# Lixieuhr-Segment.net
KiCad netlist of a schematic drawn in EAGLE
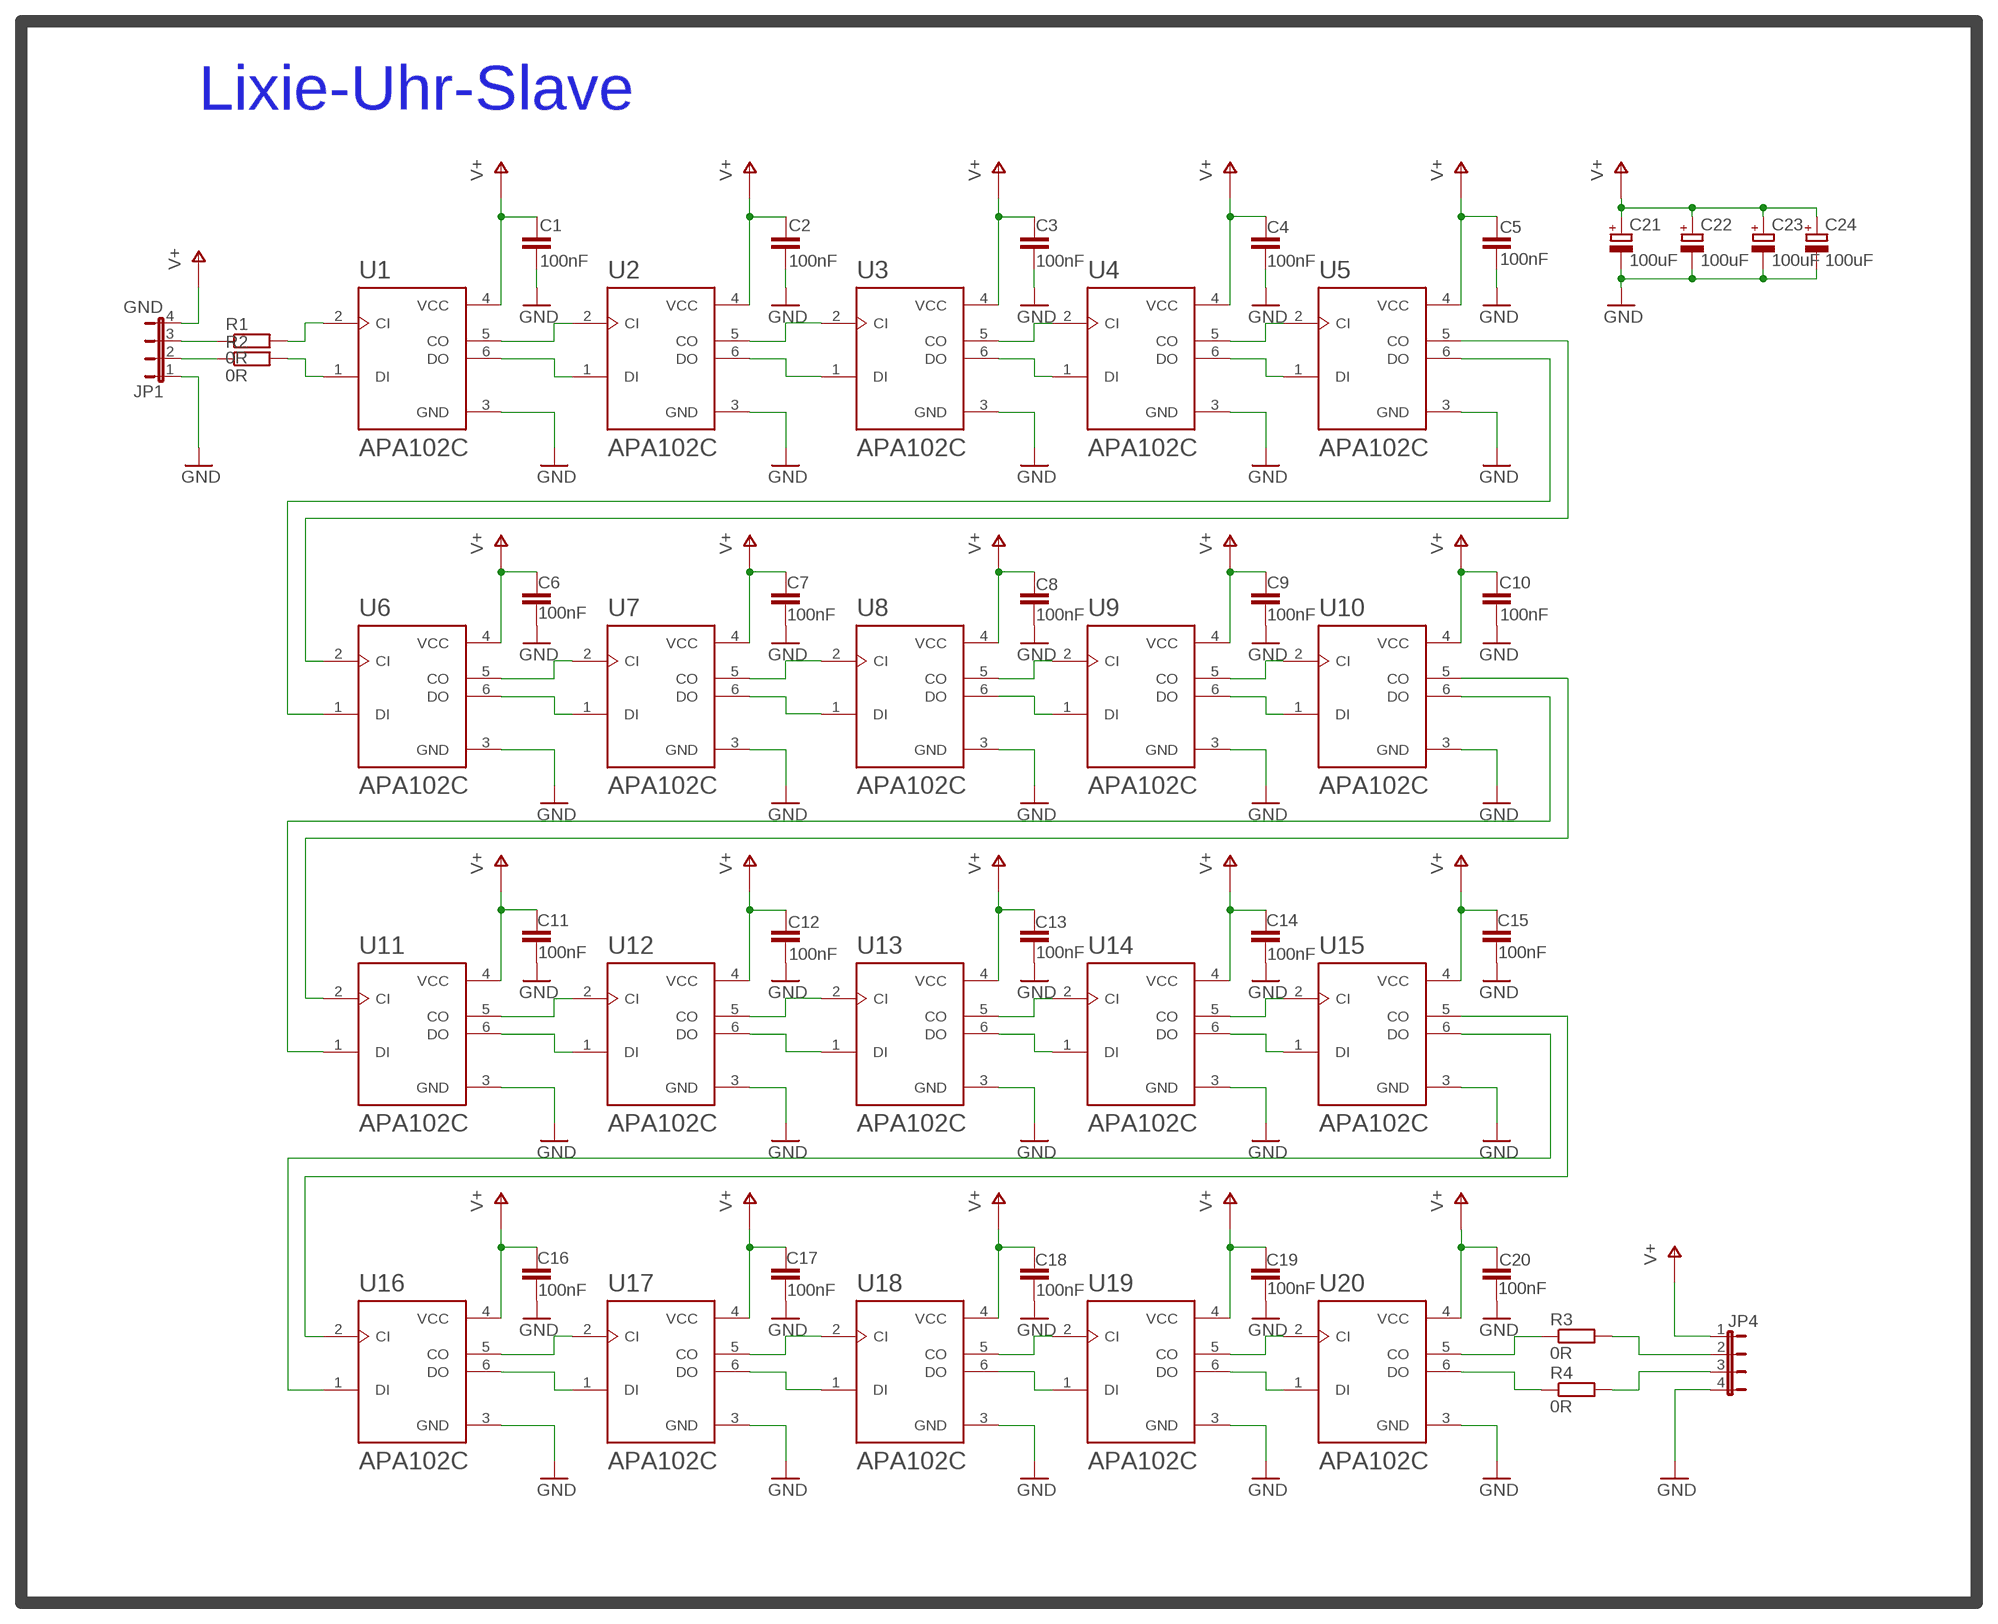
[diagram p0: schematic, sheet 1]

(export (version "E")
  (design (tool "Eeschema 10.0.6"))
  (components
    (comp (ref "C1")
      (value "100nF")
      (footprint "eagle-import:C0805")
      (libsource (lib "eagle-import") (part "C-0805"))
    )
    (comp (ref "C2")
      (value "100nF")
      (footprint "eagle-import:C0805")
      (libsource (lib "eagle-import") (part "C-0805"))
    )
    (comp (ref "C3")
      (value "100nF")
      (footprint "eagle-import:C0805")
      (libsource (lib "eagle-import") (part "C-0805"))
    )
    (comp (ref "C4")
      (value "100nF")
      (footprint "eagle-import:C0805")
      (libsource (lib "eagle-import") (part "C-0805"))
    )
    (comp (ref "C5")
      (value "100nF")
      (footprint "eagle-import:C0805")
      (libsource (lib "eagle-import") (part "C-0805"))
    )
    (comp (ref "C6")
      (value "100nF")
      (footprint "eagle-import:C0805")
      (libsource (lib "eagle-import") (part "C-0805"))
    )
    (comp (ref "C7")
      (value "100nF")
      (footprint "eagle-import:C0805")
      (libsource (lib "eagle-import") (part "C-0805"))
    )
    (comp (ref "C8")
      (value "100nF")
      (footprint "eagle-import:C0805")
      (libsource (lib "eagle-import") (part "C-0805"))
    )
    (comp (ref "C9")
      (value "100nF")
      (footprint "eagle-import:C0805")
      (libsource (lib "eagle-import") (part "C-0805"))
    )
    (comp (ref "C10")
      (value "100nF")
      (footprint "eagle-import:C0805")
      (libsource (lib "eagle-import") (part "C-0805"))
    )
    (comp (ref "C11")
      (value "100nF")
      (footprint "eagle-import:C0805")
      (libsource (lib "eagle-import") (part "C-0805"))
    )
    (comp (ref "C12")
      (value "100nF")
      (footprint "eagle-import:C0805")
      (libsource (lib "eagle-import") (part "C-0805"))
    )
    (comp (ref "C13")
      (value "100nF")
      (footprint "eagle-import:C0805")
      (libsource (lib "eagle-import") (part "C-0805"))
    )
    (comp (ref "C14")
      (value "100nF")
      (footprint "eagle-import:C0805")
      (libsource (lib "eagle-import") (part "C-0805"))
    )
    (comp (ref "C15")
      (value "100nF")
      (footprint "eagle-import:C0805")
      (libsource (lib "eagle-import") (part "C-0805"))
    )
    (comp (ref "C16")
      (value "100nF")
      (footprint "eagle-import:C0805")
      (libsource (lib "eagle-import") (part "C-0805"))
    )
    (comp (ref "C17")
      (value "100nF")
      (footprint "eagle-import:C0805")
      (libsource (lib "eagle-import") (part "C-0805"))
    )
    (comp (ref "C18")
      (value "100nF")
      (footprint "eagle-import:C0805")
      (libsource (lib "eagle-import") (part "C-0805"))
    )
    (comp (ref "C19")
      (value "100nF")
      (footprint "eagle-import:C0805")
      (libsource (lib "eagle-import") (part "C-0805"))
    )
    (comp (ref "C20")
      (value "100nF")
      (footprint "eagle-import:C0805")
      (libsource (lib "eagle-import") (part "C-0805"))
    )
    (comp (ref "C21")
      (value "100uF")
      (footprint "eagle-import:153CLV-0405")
      (libsource (lib "eagle-import") (part "CPOL-EU153CLV-0405"))
    )
    (comp (ref "C22")
      (value "100uF")
      (footprint "eagle-import:153CLV-0405")
      (libsource (lib "eagle-import") (part "CPOL-EU153CLV-0405"))
    )
    (comp (ref "C23")
      (value "100uF")
      (footprint "eagle-import:153CLV-0405")
      (libsource (lib "eagle-import") (part "CPOL-EU153CLV-0405"))
    )
    (comp (ref "C24")
      (value "100uF")
      (footprint "eagle-import:153CLV-0405")
      (libsource (lib "eagle-import") (part "CPOL-EU153CLV-0405"))
    )
    (comp (ref "JP1")
      (value "GND")
      (footprint "eagle-import:JP4")
      (libsource (lib "eagle-import") (part "JP4E"))
    )
    (comp (ref "JP4")
      (value "JP4E")
      (footprint "eagle-import:JP4")
      (libsource (lib "eagle-import") (part "JP4E"))
    )
    (comp (ref "R1")
      (value "0R")
      (footprint "eagle-import:R1206")
      (libsource (lib "eagle-import") (part "R-R1206"))
    )
    (comp (ref "R2")
      (value "0R")
      (footprint "eagle-import:R1206")
      (libsource (lib "eagle-import") (part "R-R1206"))
    )
    (comp (ref "R3")
      (value "0R")
      (footprint "eagle-import:R1206")
      (libsource (lib "eagle-import") (part "R-R1206"))
    )
    (comp (ref "R4")
      (value "0R")
      (footprint "eagle-import:R1206")
      (libsource (lib "eagle-import") (part "R-R1206"))
    )
    (comp (ref "U1")
      (value "APA102C")
      (footprint "eagle-import:SON160P500X500X140-6N")
      (fields (field (name "MF") "Shiji Lighting"))
      (libsource (lib "eagle-import") (part "APA102C"))
    )
    (comp (ref "U2")
      (value "APA102C")
      (footprint "eagle-import:SON160P500X500X140-6N")
      (fields (field (name "MF") "Shiji Lighting"))
      (libsource (lib "eagle-import") (part "APA102C"))
    )
    (comp (ref "U3")
      (value "APA102C")
      (footprint "eagle-import:SON160P500X500X140-6N")
      (fields (field (name "MF") "Shiji Lighting"))
      (libsource (lib "eagle-import") (part "APA102C"))
    )
    (comp (ref "U4")
      (value "APA102C")
      (footprint "eagle-import:SON160P500X500X140-6N")
      (fields (field (name "MF") "Shiji Lighting"))
      (libsource (lib "eagle-import") (part "APA102C"))
    )
    (comp (ref "U5")
      (value "APA102C")
      (footprint "eagle-import:SON160P500X500X140-6N")
      (fields (field (name "MF") "Shiji Lighting"))
      (libsource (lib "eagle-import") (part "APA102C"))
    )
    (comp (ref "U6")
      (value "APA102C")
      (footprint "eagle-import:SON160P500X500X140-6N")
      (fields (field (name "MF") "Shiji Lighting"))
      (libsource (lib "eagle-import") (part "APA102C"))
    )
    (comp (ref "U7")
      (value "APA102C")
      (footprint "eagle-import:SON160P500X500X140-6N")
      (fields (field (name "MF") "Shiji Lighting"))
      (libsource (lib "eagle-import") (part "APA102C"))
    )
    (comp (ref "U8")
      (value "APA102C")
      (footprint "eagle-import:SON160P500X500X140-6N")
      (fields (field (name "MF") "Shiji Lighting"))
      (libsource (lib "eagle-import") (part "APA102C"))
    )
    (comp (ref "U9")
      (value "APA102C")
      (footprint "eagle-import:SON160P500X500X140-6N")
      (fields (field (name "MF") "Shiji Lighting"))
      (libsource (lib "eagle-import") (part "APA102C"))
    )
    (comp (ref "U10")
      (value "APA102C")
      (footprint "eagle-import:SON160P500X500X140-6N")
      (fields (field (name "MF") "Shiji Lighting"))
      (libsource (lib "eagle-import") (part "APA102C"))
    )
    (comp (ref "U11")
      (value "APA102C")
      (footprint "eagle-import:SON160P500X500X140-6N")
      (fields (field (name "MF") "Shiji Lighting"))
      (libsource (lib "eagle-import") (part "APA102C"))
    )
    (comp (ref "U12")
      (value "APA102C")
      (footprint "eagle-import:SON160P500X500X140-6N")
      (fields (field (name "MF") "Shiji Lighting"))
      (libsource (lib "eagle-import") (part "APA102C"))
    )
    (comp (ref "U13")
      (value "APA102C")
      (footprint "eagle-import:SON160P500X500X140-6N")
      (fields (field (name "MF") "Shiji Lighting"))
      (libsource (lib "eagle-import") (part "APA102C"))
    )
    (comp (ref "U14")
      (value "APA102C")
      (footprint "eagle-import:SON160P500X500X140-6N")
      (fields (field (name "MF") "Shiji Lighting"))
      (libsource (lib "eagle-import") (part "APA102C"))
    )
    (comp (ref "U15")
      (value "APA102C")
      (footprint "eagle-import:SON160P500X500X140-6N")
      (fields (field (name "MF") "Shiji Lighting"))
      (libsource (lib "eagle-import") (part "APA102C"))
    )
    (comp (ref "U16")
      (value "APA102C")
      (footprint "eagle-import:SON160P500X500X140-6N")
      (fields (field (name "MF") "Shiji Lighting"))
      (libsource (lib "eagle-import") (part "APA102C"))
    )
    (comp (ref "U17")
      (value "APA102C")
      (footprint "eagle-import:SON160P500X500X140-6N")
      (fields (field (name "MF") "Shiji Lighting"))
      (libsource (lib "eagle-import") (part "APA102C"))
    )
    (comp (ref "U18")
      (value "APA102C")
      (footprint "eagle-import:SON160P500X500X140-6N")
      (fields (field (name "MF") "Shiji Lighting"))
      (libsource (lib "eagle-import") (part "APA102C"))
    )
    (comp (ref "U19")
      (value "APA102C")
      (footprint "eagle-import:SON160P500X500X140-6N")
      (fields (field (name "MF") "Shiji Lighting"))
      (libsource (lib "eagle-import") (part "APA102C"))
    )
    (comp (ref "U20")
      (value "APA102C")
      (footprint "eagle-import:SON160P500X500X140-6N")
      (fields (field (name "MF") "Shiji Lighting"))
      (libsource (lib "eagle-import") (part "APA102C"))
    )
  )
  (nets
    (net (code "1") (name "GND") (class "Default")
      (node (ref "C1") (pin "1") (pinfunction "1_1") (pintype "passive"))
      (node (ref "C10") (pin "1") (pinfunction "1_1") (pintype "passive"))
      (node (ref "C11") (pin "1") (pinfunction "1_1") (pintype "passive"))
      (node (ref "C12") (pin "1") (pinfunction "1_1") (pintype "passive"))
      (node (ref "C13") (pin "1") (pinfunction "1_1") (pintype "passive"))
      (node (ref "C14") (pin "1") (pinfunction "1_1") (pintype "passive"))
      (node (ref "C15") (pin "1") (pinfunction "1_1") (pintype "passive"))
      (node (ref "C16") (pin "1") (pinfunction "1_1") (pintype "passive"))
      (node (ref "C17") (pin "1") (pinfunction "1_1") (pintype "passive"))
      (node (ref "C18") (pin "1") (pinfunction "1_1") (pintype "passive"))
      (node (ref "C19") (pin "1") (pinfunction "1_1") (pintype "passive"))
      (node (ref "C2") (pin "1") (pinfunction "1_1") (pintype "passive"))
      (node (ref "C20") (pin "1") (pinfunction "1_1") (pintype "passive"))
      (node (ref "C21") (pin "-") (pinfunction "-_-") (pintype "passive"))
      (node (ref "C22") (pin "-") (pinfunction "-_-") (pintype "passive"))
      (node (ref "C23") (pin "-") (pinfunction "-_-") (pintype "passive"))
      (node (ref "C24") (pin "-") (pinfunction "-_-") (pintype "passive"))
      (node (ref "C3") (pin "1") (pinfunction "1_1") (pintype "passive"))
      (node (ref "C4") (pin "1") (pinfunction "1_1") (pintype "passive"))
      (node (ref "C5") (pin "1") (pinfunction "1_1") (pintype "passive"))
      (node (ref "C6") (pin "1") (pinfunction "1_1") (pintype "passive"))
      (node (ref "C7") (pin "1") (pinfunction "1_1") (pintype "passive"))
      (node (ref "C8") (pin "1") (pinfunction "1_1") (pintype "passive"))
      (node (ref "C9") (pin "1") (pinfunction "1_1") (pintype "passive"))
      (node (ref "JP1") (pin "1") (pinfunction "1_1") (pintype "passive"))
      (node (ref "JP4") (pin "4") (pinfunction "4_4") (pintype "passive"))
      (node (ref "U1") (pin "3") (pinfunction "GND_3") (pintype "power_in"))
      (node (ref "U10") (pin "3") (pinfunction "GND_3") (pintype "power_in"))
      (node (ref "U11") (pin "3") (pinfunction "GND_3") (pintype "power_in"))
      (node (ref "U12") (pin "3") (pinfunction "GND_3") (pintype "power_in"))
      (node (ref "U13") (pin "3") (pinfunction "GND_3") (pintype "power_in"))
      (node (ref "U14") (pin "3") (pinfunction "GND_3") (pintype "power_in"))
      (node (ref "U15") (pin "3") (pinfunction "GND_3") (pintype "power_in"))
      (node (ref "U16") (pin "3") (pinfunction "GND_3") (pintype "power_in"))
      (node (ref "U17") (pin "3") (pinfunction "GND_3") (pintype "power_in"))
      (node (ref "U18") (pin "3") (pinfunction "GND_3") (pintype "power_in"))
      (node (ref "U19") (pin "3") (pinfunction "GND_3") (pintype "power_in"))
      (node (ref "U2") (pin "3") (pinfunction "GND_3") (pintype "power_in"))
      (node (ref "U20") (pin "3") (pinfunction "GND_3") (pintype "power_in"))
      (node (ref "U3") (pin "3") (pinfunction "GND_3") (pintype "power_in"))
      (node (ref "U4") (pin "3") (pinfunction "GND_3") (pintype "power_in"))
      (node (ref "U5") (pin "3") (pinfunction "GND_3") (pintype "power_in"))
      (node (ref "U6") (pin "3") (pinfunction "GND_3") (pintype "power_in"))
      (node (ref "U7") (pin "3") (pinfunction "GND_3") (pintype "power_in"))
      (node (ref "U8") (pin "3") (pinfunction "GND_3") (pintype "power_in"))
      (node (ref "U9") (pin "3") (pinfunction "GND_3") (pintype "power_in"))
    )
    (net (code "2") (name "Net-(JP1-Pad2)") (class "Default")
      (node (ref "JP1") (pin "2") (pinfunction "2_2") (pintype "passive"))
      (node (ref "R2") (pin "1") (pinfunction "1_1") (pintype "passive"))
    )
    (net (code "3") (name "Net-(JP1-Pad3)") (class "Default")
      (node (ref "JP1") (pin "3") (pinfunction "3_3") (pintype "passive"))
      (node (ref "R1") (pin "1") (pinfunction "1_1") (pintype "passive"))
    )
    (net (code "4") (name "Net-(JP4-Pad2)") (class "Default")
      (node (ref "JP4") (pin "2") (pinfunction "2_2") (pintype "passive"))
      (node (ref "R3") (pin "2") (pinfunction "2_2") (pintype "passive"))
    )
    (net (code "5") (name "Net-(JP4-Pad3)") (class "Default")
      (node (ref "JP4") (pin "3") (pinfunction "3_3") (pintype "passive"))
      (node (ref "R4") (pin "2") (pinfunction "2_2") (pintype "passive"))
    )
    (net (code "6") (name "Net-(U1-CI)") (class "Default")
      (node (ref "R1") (pin "2") (pinfunction "2_2") (pintype "passive"))
      (node (ref "U1") (pin "2") (pinfunction "CI_2") (pintype "input"))
    )
    (net (code "7") (name "Net-(U1-CO)") (class "Default")
      (node (ref "U1") (pin "5") (pinfunction "CO_5") (pintype "output"))
      (node (ref "U2") (pin "2") (pinfunction "CI_2") (pintype "input"))
    )
    (net (code "8") (name "Net-(U1-DI)") (class "Default")
      (node (ref "R2") (pin "2") (pinfunction "2_2") (pintype "passive"))
      (node (ref "U1") (pin "1") (pinfunction "DI_1") (pintype "input"))
    )
    (net (code "9") (name "Net-(U1-DO)") (class "Default")
      (node (ref "U1") (pin "6") (pinfunction "DO_6") (pintype "output"))
      (node (ref "U2") (pin "1") (pinfunction "DI_1") (pintype "input"))
    )
    (net (code "10") (name "Net-(U2-CO)") (class "Default")
      (node (ref "U2") (pin "5") (pinfunction "CO_5") (pintype "output"))
      (node (ref "U3") (pin "2") (pinfunction "CI_2") (pintype "input"))
    )
    (net (code "11") (name "Net-(U2-DO)") (class "Default")
      (node (ref "U2") (pin "6") (pinfunction "DO_6") (pintype "output"))
      (node (ref "U3") (pin "1") (pinfunction "DI_1") (pintype "input"))
    )
    (net (code "12") (name "Net-(U3-CO)") (class "Default")
      (node (ref "U3") (pin "5") (pinfunction "CO_5") (pintype "output"))
      (node (ref "U4") (pin "2") (pinfunction "CI_2") (pintype "input"))
    )
    (net (code "13") (name "Net-(U3-DO)") (class "Default")
      (node (ref "U3") (pin "6") (pinfunction "DO_6") (pintype "output"))
      (node (ref "U4") (pin "1") (pinfunction "DI_1") (pintype "input"))
    )
    (net (code "14") (name "Net-(U4-CO)") (class "Default")
      (node (ref "U4") (pin "5") (pinfunction "CO_5") (pintype "output"))
      (node (ref "U5") (pin "2") (pinfunction "CI_2") (pintype "input"))
    )
    (net (code "15") (name "Net-(U4-DO)") (class "Default")
      (node (ref "U4") (pin "6") (pinfunction "DO_6") (pintype "output"))
      (node (ref "U5") (pin "1") (pinfunction "DI_1") (pintype "input"))
    )
    (net (code "16") (name "Net-(U5-CO)") (class "Default")
      (node (ref "U5") (pin "5") (pinfunction "CO_5") (pintype "output"))
      (node (ref "U6") (pin "2") (pinfunction "CI_2") (pintype "input"))
    )
    (net (code "17") (name "Net-(U5-DO)") (class "Default")
      (node (ref "U5") (pin "6") (pinfunction "DO_6") (pintype "output"))
      (node (ref "U6") (pin "1") (pinfunction "DI_1") (pintype "input"))
    )
    (net (code "18") (name "Net-(U6-CO)") (class "Default")
      (node (ref "U6") (pin "5") (pinfunction "CO_5") (pintype "output"))
      (node (ref "U7") (pin "2") (pinfunction "CI_2") (pintype "input"))
    )
    (net (code "19") (name "Net-(U6-DO)") (class "Default")
      (node (ref "U6") (pin "6") (pinfunction "DO_6") (pintype "output"))
      (node (ref "U7") (pin "1") (pinfunction "DI_1") (pintype "input"))
    )
    (net (code "20") (name "Net-(U7-CO)") (class "Default")
      (node (ref "U7") (pin "5") (pinfunction "CO_5") (pintype "output"))
      (node (ref "U8") (pin "2") (pinfunction "CI_2") (pintype "input"))
    )
    (net (code "21") (name "Net-(U7-DO)") (class "Default")
      (node (ref "U7") (pin "6") (pinfunction "DO_6") (pintype "output"))
      (node (ref "U8") (pin "1") (pinfunction "DI_1") (pintype "input"))
    )
    (net (code "22") (name "Net-(U8-CO)") (class "Default")
      (node (ref "U8") (pin "5") (pinfunction "CO_5") (pintype "output"))
      (node (ref "U9") (pin "2") (pinfunction "CI_2") (pintype "input"))
    )
    (net (code "23") (name "Net-(U8-DO)") (class "Default")
      (node (ref "U8") (pin "6") (pinfunction "DO_6") (pintype "output"))
      (node (ref "U9") (pin "1") (pinfunction "DI_1") (pintype "input"))
    )
    (net (code "24") (name "Net-(U10-CI)") (class "Default")
      (node (ref "U10") (pin "2") (pinfunction "CI_2") (pintype "input"))
      (node (ref "U9") (pin "5") (pinfunction "CO_5") (pintype "output"))
    )
    (net (code "25") (name "Net-(U10-CO)") (class "Default")
      (node (ref "U10") (pin "5") (pinfunction "CO_5") (pintype "output"))
      (node (ref "U11") (pin "2") (pinfunction "CI_2") (pintype "input"))
    )
    (net (code "26") (name "Net-(U10-DI)") (class "Default")
      (node (ref "U10") (pin "1") (pinfunction "DI_1") (pintype "input"))
      (node (ref "U9") (pin "6") (pinfunction "DO_6") (pintype "output"))
    )
    (net (code "27") (name "Net-(U10-DO)") (class "Default")
      (node (ref "U10") (pin "6") (pinfunction "DO_6") (pintype "output"))
      (node (ref "U11") (pin "1") (pinfunction "DI_1") (pintype "input"))
    )
    (net (code "28") (name "Net-(U11-CO)") (class "Default")
      (node (ref "U11") (pin "5") (pinfunction "CO_5") (pintype "output"))
      (node (ref "U12") (pin "2") (pinfunction "CI_2") (pintype "input"))
    )
    (net (code "29") (name "Net-(U11-DO)") (class "Default")
      (node (ref "U11") (pin "6") (pinfunction "DO_6") (pintype "output"))
      (node (ref "U12") (pin "1") (pinfunction "DI_1") (pintype "input"))
    )
    (net (code "30") (name "Net-(U12-CO)") (class "Default")
      (node (ref "U12") (pin "5") (pinfunction "CO_5") (pintype "output"))
      (node (ref "U13") (pin "2") (pinfunction "CI_2") (pintype "input"))
    )
    (net (code "31") (name "Net-(U12-DO)") (class "Default")
      (node (ref "U12") (pin "6") (pinfunction "DO_6") (pintype "output"))
      (node (ref "U13") (pin "1") (pinfunction "DI_1") (pintype "input"))
    )
    (net (code "32") (name "Net-(U13-CO)") (class "Default")
      (node (ref "U13") (pin "5") (pinfunction "CO_5") (pintype "output"))
      (node (ref "U14") (pin "2") (pinfunction "CI_2") (pintype "input"))
    )
    (net (code "33") (name "Net-(U13-DO)") (class "Default")
      (node (ref "U13") (pin "6") (pinfunction "DO_6") (pintype "output"))
      (node (ref "U14") (pin "1") (pinfunction "DI_1") (pintype "input"))
    )
    (net (code "34") (name "Net-(U14-CO)") (class "Default")
      (node (ref "U14") (pin "5") (pinfunction "CO_5") (pintype "output"))
      (node (ref "U15") (pin "2") (pinfunction "CI_2") (pintype "input"))
    )
    (net (code "35") (name "Net-(U14-DO)") (class "Default")
      (node (ref "U14") (pin "6") (pinfunction "DO_6") (pintype "output"))
      (node (ref "U15") (pin "1") (pinfunction "DI_1") (pintype "input"))
    )
    (net (code "36") (name "Net-(U15-CO)") (class "Default")
      (node (ref "U15") (pin "5") (pinfunction "CO_5") (pintype "output"))
      (node (ref "U16") (pin "2") (pinfunction "CI_2") (pintype "input"))
    )
    (net (code "37") (name "Net-(U15-DO)") (class "Default")
      (node (ref "U15") (pin "6") (pinfunction "DO_6") (pintype "output"))
      (node (ref "U16") (pin "1") (pinfunction "DI_1") (pintype "input"))
    )
    (net (code "38") (name "Net-(U16-CO)") (class "Default")
      (node (ref "U16") (pin "5") (pinfunction "CO_5") (pintype "output"))
      (node (ref "U17") (pin "2") (pinfunction "CI_2") (pintype "input"))
    )
    (net (code "39") (name "Net-(U16-DO)") (class "Default")
      (node (ref "U16") (pin "6") (pinfunction "DO_6") (pintype "output"))
      (node (ref "U17") (pin "1") (pinfunction "DI_1") (pintype "input"))
    )
    (net (code "40") (name "Net-(U17-CO)") (class "Default")
      (node (ref "U17") (pin "5") (pinfunction "CO_5") (pintype "output"))
      (node (ref "U18") (pin "2") (pinfunction "CI_2") (pintype "input"))
    )
    (net (code "41") (name "Net-(U17-DO)") (class "Default")
      (node (ref "U17") (pin "6") (pinfunction "DO_6") (pintype "output"))
      (node (ref "U18") (pin "1") (pinfunction "DI_1") (pintype "input"))
    )
    (net (code "42") (name "Net-(U18-CO)") (class "Default")
      (node (ref "U18") (pin "5") (pinfunction "CO_5") (pintype "output"))
      (node (ref "U19") (pin "2") (pinfunction "CI_2") (pintype "input"))
    )
    (net (code "43") (name "Net-(U18-DO)") (class "Default")
      (node (ref "U18") (pin "6") (pinfunction "DO_6") (pintype "output"))
      (node (ref "U19") (pin "1") (pinfunction "DI_1") (pintype "input"))
    )
    (net (code "44") (name "Net-(U19-CO)") (class "Default")
      (node (ref "U19") (pin "5") (pinfunction "CO_5") (pintype "output"))
      (node (ref "U20") (pin "2") (pinfunction "CI_2") (pintype "input"))
    )
    (net (code "45") (name "Net-(U19-DO)") (class "Default")
      (node (ref "U19") (pin "6") (pinfunction "DO_6") (pintype "output"))
      (node (ref "U20") (pin "1") (pinfunction "DI_1") (pintype "input"))
    )
    (net (code "46") (name "Net-(U20-CO)") (class "Default")
      (node (ref "R3") (pin "1") (pinfunction "1_1") (pintype "passive"))
      (node (ref "U20") (pin "5") (pinfunction "CO_5") (pintype "output"))
    )
    (net (code "47") (name "Net-(U20-DO)") (class "Default")
      (node (ref "R4") (pin "1") (pinfunction "1_1") (pintype "passive"))
      (node (ref "U20") (pin "6") (pinfunction "DO_6") (pintype "output"))
    )
    (net (code "48") (name "V+") (class "Default")
      (node (ref "C1") (pin "2") (pinfunction "2_2") (pintype "passive"))
      (node (ref "C10") (pin "2") (pinfunction "2_2") (pintype "passive"))
      (node (ref "C11") (pin "2") (pinfunction "2_2") (pintype "passive"))
      (node (ref "C12") (pin "2") (pinfunction "2_2") (pintype "passive"))
      (node (ref "C13") (pin "2") (pinfunction "2_2") (pintype "passive"))
      (node (ref "C14") (pin "2") (pinfunction "2_2") (pintype "passive"))
      (node (ref "C15") (pin "2") (pinfunction "2_2") (pintype "passive"))
      (node (ref "C16") (pin "2") (pinfunction "2_2") (pintype "passive"))
      (node (ref "C17") (pin "2") (pinfunction "2_2") (pintype "passive"))
      (node (ref "C18") (pin "2") (pinfunction "2_2") (pintype "passive"))
      (node (ref "C19") (pin "2") (pinfunction "2_2") (pintype "passive"))
      (node (ref "C2") (pin "2") (pinfunction "2_2") (pintype "passive"))
      (node (ref "C20") (pin "2") (pinfunction "2_2") (pintype "passive"))
      (node (ref "C21") (pin "+") (pinfunction "+_+") (pintype "passive"))
      (node (ref "C22") (pin "+") (pinfunction "+_+") (pintype "passive"))
      (node (ref "C23") (pin "+") (pinfunction "+_+") (pintype "passive"))
      (node (ref "C24") (pin "+") (pinfunction "+_+") (pintype "passive"))
      (node (ref "C3") (pin "2") (pinfunction "2_2") (pintype "passive"))
      (node (ref "C4") (pin "2") (pinfunction "2_2") (pintype "passive"))
      (node (ref "C5") (pin "2") (pinfunction "2_2") (pintype "passive"))
      (node (ref "C6") (pin "2") (pinfunction "2_2") (pintype "passive"))
      (node (ref "C7") (pin "2") (pinfunction "2_2") (pintype "passive"))
      (node (ref "C8") (pin "2") (pinfunction "2_2") (pintype "passive"))
      (node (ref "C9") (pin "2") (pinfunction "2_2") (pintype "passive"))
      (node (ref "JP1") (pin "4") (pinfunction "4_4") (pintype "passive"))
      (node (ref "JP4") (pin "1") (pinfunction "1_1") (pintype "passive"))
      (node (ref "U1") (pin "4") (pinfunction "VCC_4") (pintype "power_in"))
      (node (ref "U10") (pin "4") (pinfunction "VCC_4") (pintype "power_in"))
      (node (ref "U11") (pin "4") (pinfunction "VCC_4") (pintype "power_in"))
      (node (ref "U12") (pin "4") (pinfunction "VCC_4") (pintype "power_in"))
      (node (ref "U13") (pin "4") (pinfunction "VCC_4") (pintype "power_in"))
      (node (ref "U14") (pin "4") (pinfunction "VCC_4") (pintype "power_in"))
      (node (ref "U15") (pin "4") (pinfunction "VCC_4") (pintype "power_in"))
      (node (ref "U16") (pin "4") (pinfunction "VCC_4") (pintype "power_in"))
      (node (ref "U17") (pin "4") (pinfunction "VCC_4") (pintype "power_in"))
      (node (ref "U18") (pin "4") (pinfunction "VCC_4") (pintype "power_in"))
      (node (ref "U19") (pin "4") (pinfunction "VCC_4") (pintype "power_in"))
      (node (ref "U2") (pin "4") (pinfunction "VCC_4") (pintype "power_in"))
      (node (ref "U20") (pin "4") (pinfunction "VCC_4") (pintype "power_in"))
      (node (ref "U3") (pin "4") (pinfunction "VCC_4") (pintype "power_in"))
      (node (ref "U4") (pin "4") (pinfunction "VCC_4") (pintype "power_in"))
      (node (ref "U5") (pin "4") (pinfunction "VCC_4") (pintype "power_in"))
      (node (ref "U6") (pin "4") (pinfunction "VCC_4") (pintype "power_in"))
      (node (ref "U7") (pin "4") (pinfunction "VCC_4") (pintype "power_in"))
      (node (ref "U8") (pin "4") (pinfunction "VCC_4") (pintype "power_in"))
      (node (ref "U9") (pin "4") (pinfunction "VCC_4") (pintype "power_in"))
    )
  )
)
